# OZ440-SE100-CAR003_sheet12.net
KiCad netlist of a schematic drawn in Altium Designer
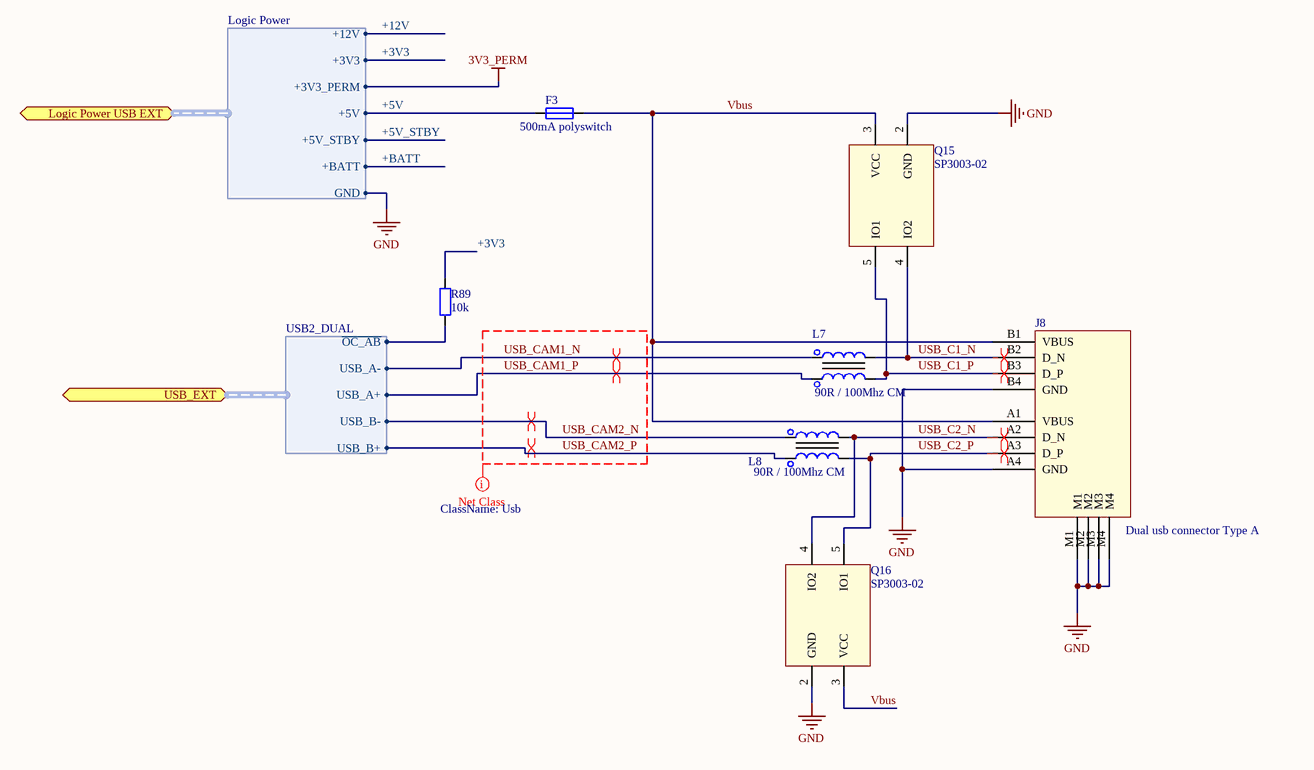
[diagram p0: OZ440-SE100-CAR003_sheet12.SchDoc]

(export (version "E")
  (design (tool "Eeschema 10.0.6"))
  (components
    (comp (ref "F3")
      (value "FUSE-SMD")
      (footprint "R0805-STD")
      (description "0805 500mA resettable fuse")
      (fields (field (name "DISPLAYED REFERENCE") "500mA polyswitch") (field (name "MANUFACTURER") "BOURNS"))
      (libsource (lib "lib_NAIO") (part "FUSE-SMD"))
    )
    (comp (ref "J8")
      (value "CONN-STD_USB_A_DUAL")
      (footprint "CONN-STD-USB_A")
      (description "Dual USB Type A connector")
      (fields
        (field (name "DISPLAYED REFERENCE") "Dual usb connector Type A")
        (field (name "MANUFACTURER") "FCI")
      )
      (libsource (lib "lib_NAIO") (part "CONN-STD_USB_A_DUAL"))
    )
    (comp (ref "L7")
      (value "IND-MC-SMD")
      (footprint "L-SPE-0805_MC_EXC34")
      (description "USB common mode inductor")
      (fields
        (field (name "DISPLAYED REFERENCE") "90R / 100Mhz CM")
        (field (name "MANUFACTURER") "PANASONIC")
      )
      (libsource (lib "lib_NAIO") (part "IND-MC-SMD"))
    )
    (comp (ref "L8")
      (value "IND-MC-SMD")
      (footprint "L-SPE-0805_MC_EXC34")
      (description "USB common mode inductor")
      (fields
        (field (name "DISPLAYED REFERENCE") "90R / 100Mhz CM")
        (field (name "MANUFACTURER") "PANASONIC")
      )
      (libsource (lib "lib_NAIO") (part "IND-MC-SMD"))
    )
    (comp (ref "Q15")
      (value "SP03003_02-SC70")
      (footprint "SC70-SPE-SP3003")
      (description "Low capacitance ESD TVS")
      (fields (field (name "DISPLAYED REFERENCE") "SP3003-02") (field (name "MANUFACTURER") "LITTLEFUSE"))
      (libsource (lib "") (part "SP03003_02-SC70_1"))
    )
    (comp (ref "Q16")
      (value "SP03003_02-SC70")
      (footprint "SC70-SPE-SP3003")
      (description "Low capacitance ESD TVS")
      (fields (field (name "DISPLAYED REFERENCE") "SP3003-02") (field (name "MANUFACTURER") "LITTLEFUSE"))
      (libsource (lib "lib_NAIO") (part "SP03003_02-SC70"))
    )
    (comp (ref "R89")
      (value "RES-SMD")
      (footprint "R0805-STD")
      (description "10k Ohm 0805 SMD resistor")
      (fields
        (field (name "DISPLAYED REFERENCE") "10k")
        (field (name "TOLERANCE") "1 %")
        (field (name "MANUFACTURER") "Vishay")
      )
      (libsource (lib "lib_NAIO") (part "RES-SMD"))
    )
  )
  (nets
    (net (code "4") (name "/+3V3") (class "Default")
      (node (ref "R89") (pin "2") (pinfunction "2_2") (pintype "passive"))
    )
    (net (code "5") (name "/+5V") (class "Default")
      (node (ref "F3") (pin "1") (pinfunction "1_1") (pintype "passive"))
    )
    (net (code "9") (name "/USB_C1_N") (class "Default")
      (node (ref "J8") (pin "B2") (pinfunction "D_N_B2") (pintype "passive"))
      (node (ref "L7") (pin "2") (pinfunction "2_2") (pintype "passive"))
      (node (ref "Q15") (pin "4") (pinfunction "IO2_4") (pintype "passive"))
    )
    (net (code "10") (name "/USB_C1_P") (class "Default")
      (node (ref "J8") (pin "B3") (pinfunction "D_P_B3") (pintype "passive"))
      (node (ref "L7") (pin "3") (pinfunction "3_3") (pintype "passive"))
      (node (ref "Q15") (pin "5") (pinfunction "IO1_5") (pintype "passive"))
    )
    (net (code "11") (name "/USB_C2_N") (class "Default")
      (node (ref "J8") (pin "A2") (pinfunction "D_N_A2") (pintype "passive"))
      (node (ref "L8") (pin "2") (pinfunction "2_2") (pintype "passive"))
      (node (ref "Q16") (pin "4") (pinfunction "IO2_4") (pintype "passive"))
    )
    (net (code "12") (name "/USB_C2_P") (class "Default")
      (node (ref "J8") (pin "A3") (pinfunction "D_P_A3") (pintype "passive"))
      (node (ref "L8") (pin "3") (pinfunction "3_3") (pintype "passive"))
      (node (ref "Q16") (pin "5") (pinfunction "IO1_5") (pintype "passive"))
    )
    (net (code "13") (name "/USB_CAM1_N") (class "Default")
      (node (ref "L7") (pin "1") (pinfunction "1_1") (pintype "passive"))
    )
    (net (code "14") (name "/USB_CAM1_P") (class "Default")
      (node (ref "L7") (pin "4") (pinfunction "4_4") (pintype "passive"))
    )
    (net (code "15") (name "/USB_CAM2_N") (class "Default")
      (node (ref "L8") (pin "1") (pinfunction "1_1") (pintype "passive"))
    )
    (net (code "16") (name "/USB_CAM2_P") (class "Default")
      (node (ref "L8") (pin "4") (pinfunction "4_4") (pintype "passive"))
    )
    (net (code "17") (name "/Vbus") (class "Default")
      (node (ref "F3") (pin "2") (pinfunction "2_2") (pintype "passive"))
      (node (ref "J8") (pin "A1") (pinfunction "VBUS_A1") (pintype "passive"))
      (node (ref "J8") (pin "B1") (pinfunction "VBUS_B1") (pintype "passive"))
      (node (ref "Q15") (pin "3") (pinfunction "VCC_3") (pintype "passive"))
      (node (ref "Q16") (pin "3") (pinfunction "VCC_3") (pintype "passive"))
    )
    (net (code "20") (name "/~{OC_AB}") (class "Default")
      (node (ref "R89") (pin "1") (pinfunction "1_1") (pintype "passive"))
    )
    (net (code "22") (name "GND") (class "Default")
      (node (ref "J8") (pin "A4") (pinfunction "GND_A4") (pintype "passive"))
      (node (ref "J8") (pin "B4") (pinfunction "GND_B4") (pintype "passive"))
      (node (ref "J8") (pin "M1") (pinfunction "M1_M1") (pintype "passive"))
      (node (ref "J8") (pin "M2") (pinfunction "M2_M2") (pintype "passive"))
      (node (ref "J8") (pin "M3") (pinfunction "M3_M3") (pintype "passive"))
      (node (ref "J8") (pin "M4") (pinfunction "M4_M4") (pintype "passive"))
      (node (ref "Q15") (pin "2") (pinfunction "GND_2") (pintype "passive"))
      (node (ref "Q16") (pin "2") (pinfunction "GND_2") (pintype "passive"))
    )
  )
)
